# NeopixelRGBVisualizer-Single.net
KiCad netlist of a schematic drawn in EAGLE
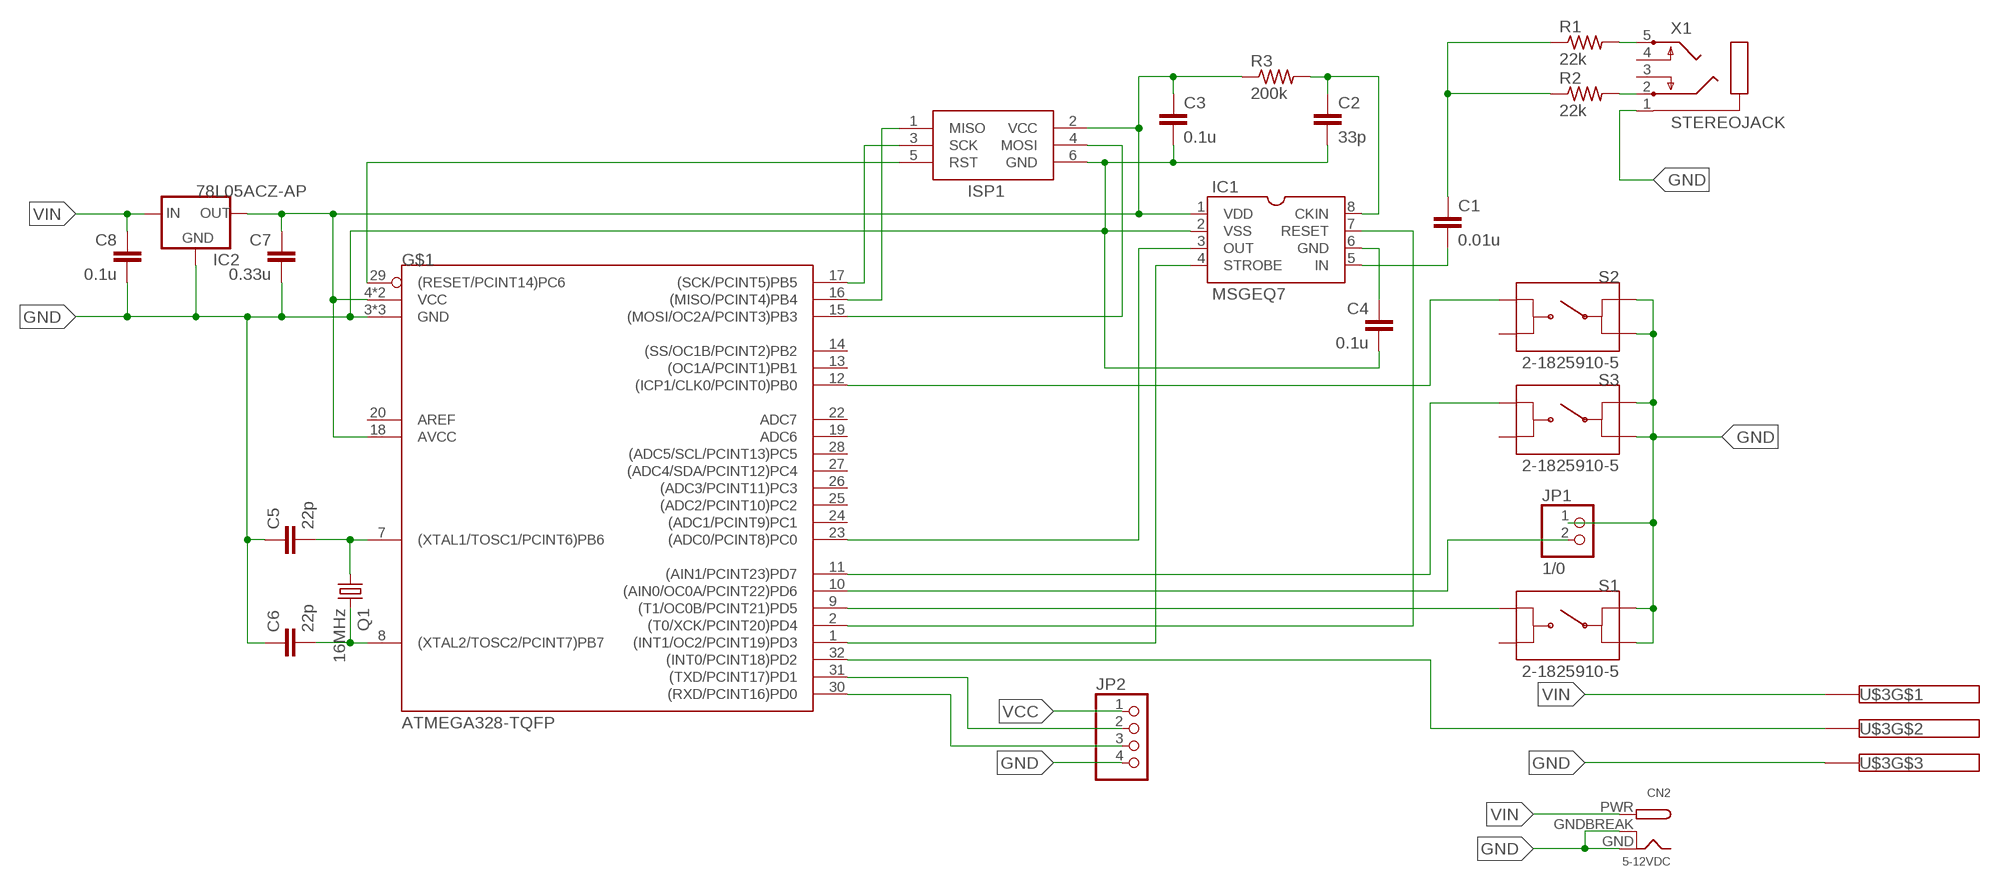
[diagram p0: schematic, sheet 1]

(export (version "E")
  (design (tool "Eeschema 10.0.6"))
  (components
    (comp (ref "C1")
      (value "0.01u")
      (footprint "eagle-import:C0805")
      (libsource (lib "eagle-import") (part "C-EUC0805"))
    )
    (comp (ref "C2")
      (value "33p")
      (footprint "eagle-import:C0805")
      (libsource (lib "eagle-import") (part "C-EUC0805"))
    )
    (comp (ref "C3")
      (value "0.1u")
      (footprint "eagle-import:C0805")
      (libsource (lib "eagle-import") (part "C-EUC0805"))
    )
    (comp (ref "C4")
      (value "0.1u")
      (footprint "eagle-import:C0805")
      (libsource (lib "eagle-import") (part "C-EUC0805"))
    )
    (comp (ref "C5")
      (value "22p")
      (footprint "eagle-import:C0805")
      (libsource (lib "eagle-import") (part "C-EUC0805"))
    )
    (comp (ref "C6")
      (value "22p")
      (footprint "eagle-import:C0805")
      (libsource (lib "eagle-import") (part "C-EUC0805"))
    )
    (comp (ref "C7")
      (value "0.33u")
      (footprint "eagle-import:C0805")
      (libsource (lib "eagle-import") (part "C-EUC0805"))
    )
    (comp (ref "C8")
      (value "0.1u")
      (footprint "eagle-import:C0805")
      (libsource (lib "eagle-import") (part "C-EUC0805"))
    )
    (comp (ref "CN2")
      (value "5-12VDC")
      (footprint "eagle-import:DCJACK_2MM_PTH")
      (libsource (lib "eagle-import") (part "DCBARRELPTH"))
    )
    (comp (ref "IC1")
      (value "MSGEQ7")
      (footprint "eagle-import:DIL08")
      (libsource (lib "eagle-import") (part "MSGEQ7"))
    )
    (comp (ref "IC2")
      (value "78L05ACZ-AP")
      (footprint "eagle-import:78LXX")
      (libsource (lib "eagle-import") (part "78LXX"))
    )
    (comp (ref "ISP1")
      (value "AVRISP-6")
      (footprint "eagle-import:AVRISP")
      (libsource (lib "eagle-import") (part "AVRISP-6"))
    )
    (comp (ref "JP1")
      (value "1/0")
      (footprint "eagle-import:1X02-ROUND")
      (libsource (lib "eagle-import") (part "PINHD-1X2/ROUND"))
    )
    (comp (ref "JP2")
      (value "PINHD-1X4/OCT")
      (footprint "eagle-import:1X04-OCT")
      (libsource (lib "eagle-import") (part "PINHD-1X4/OCT"))
    )
    (comp (ref "Q1")
      (value "16MHz")
      (footprint "eagle-import:CTS406")
      (libsource (lib "eagle-import") (part "CRYSTALCTS406"))
    )
    (comp (ref "R1")
      (value "22k")
      (footprint "eagle-import:M0805")
      (libsource (lib "eagle-import") (part "R-US_M0805"))
    )
    (comp (ref "R2")
      (value "22k")
      (footprint "eagle-import:M0805")
      (libsource (lib "eagle-import") (part "R-US_M0805"))
    )
    (comp (ref "R3")
      (value "200k")
      (footprint "eagle-import:M0805")
      (libsource (lib "eagle-import") (part "R-US_M0805"))
    )
    (comp (ref "S1")
      (value "2-1825910-5")
      (footprint "eagle-import:SW_2-1825910")
      (fields (field (name "DIGI-KEY_PART_NUMBER") "450-1644-ND") (field (name "MF") "TE Connectivity"))
      (libsource (lib "eagle-import") (part "2-1825910-5"))
    )
    (comp (ref "S2")
      (value "2-1825910-5")
      (footprint "eagle-import:SW_2-1825910")
      (fields (field (name "DIGI-KEY_PART_NUMBER") "450-1644-ND") (field (name "MF") "TE Connectivity"))
      (libsource (lib "eagle-import") (part "2-1825910-5"))
    )
    (comp (ref "S3")
      (value "2-1825910-5")
      (footprint "eagle-import:SW_2-1825910")
      (fields (field (name "DIGI-KEY_PART_NUMBER") "450-1644-ND") (field (name "MF") "TE Connectivity"))
      (libsource (lib "eagle-import") (part "2-1825910-5"))
    )
    (comp (ref "U$1")
      (value "ATMEGA328-TQFP")
      (footprint "eagle-import:32M1-A")
      (libsource (lib "eagle-import") (part "ATMEGA328-TQFP"))
    )
    (comp (ref "U$3")
      (value "0039303035")
      (footprint "eagle-import:4.2MM-3PIN")
      (libsource (lib "eagle-import") (part "0039303035"))
    )
    (comp (ref "X1")
      (value "STEREOJACK")
      (footprint "eagle-import:STX3100")
      (libsource (lib "eagle-import") (part "STEREOJACK"))
    )
  )
  (nets
    (net (code "1") (name "GND") (class "Default")
      (node (ref "C2") (pin "2") (pinfunction "2_2") (pintype "passive"))
      (node (ref "C3") (pin "2") (pinfunction "2_2") (pintype "passive"))
      (node (ref "C4") (pin "2") (pinfunction "2_2") (pintype "passive"))
      (node (ref "C5") (pin "1") (pinfunction "1_1") (pintype "passive"))
      (node (ref "C6") (pin "1") (pinfunction "1_1") (pintype "passive"))
      (node (ref "C7") (pin "2") (pinfunction "2_2") (pintype "passive"))
      (node (ref "C8") (pin "2") (pinfunction "2_2") (pintype "passive"))
      (node (ref "CN2") (pin "GND") (pinfunction "GND_GND") (pintype "power_in"))
      (node (ref "CN2") (pin "GNDBREAK") (pinfunction "GNDBREAK_GNDBREAK") (pintype "power_in"))
      (node (ref "IC1") (pin "2") (pinfunction "VSS_2") (pintype "passive"))
      (node (ref "IC2") (pin "GND") (pinfunction "GND_GND") (pintype "input"))
      (node (ref "ISP1") (pin "6") (pinfunction "GND_6") (pintype "power_in"))
      (node (ref "JP1") (pin "1") (pinfunction "1_1") (pintype "passive"))
      (node (ref "JP2") (pin "4") (pinfunction "4_4") (pintype "passive"))
      (node (ref "S1") (pin "1") (pinfunction "1_1") (pintype "passive"))
      (node (ref "S1") (pin "3") (pinfunction "3_3") (pintype "passive"))
      (node (ref "S2") (pin "1") (pinfunction "1_1") (pintype "passive"))
      (node (ref "S2") (pin "3") (pinfunction "3_3") (pintype "passive"))
      (node (ref "S3") (pin "1") (pinfunction "1_1") (pintype "passive"))
      (node (ref "S3") (pin "3") (pinfunction "3_3") (pintype "passive"))
      (node (ref "U$1") (pin "21") (pinfunction "GND_21") (pintype "bidirectional"))
      (node (ref "U$1") (pin "3") (pinfunction "GND_3") (pintype "bidirectional"))
      (node (ref "U$1") (pin "5") (pinfunction "GND_5") (pintype "bidirectional"))
      (node (ref "U$3") (pin "P$3") (pinfunction "P$1_P$3") (pintype "bidirectional"))
      (node (ref "X1") (pin "1") (pinfunction "1_1") (pintype "passive"))
    )
    (net (code "2") (name "Net-(C1-Pad1)") (class "Default")
      (node (ref "C1") (pin "1") (pinfunction "1_1") (pintype "passive"))
      (node (ref "R1") (pin "1") (pinfunction "1_1") (pintype "passive"))
      (node (ref "R2") (pin "1") (pinfunction "1_1") (pintype "passive"))
    )
    (net (code "3") (name "Net-(IC1-CKIN)") (class "Default")
      (node (ref "C2") (pin "1") (pinfunction "1_1") (pintype "passive"))
      (node (ref "IC1") (pin "8") (pinfunction "CKIN_8") (pintype "passive"))
      (node (ref "R3") (pin "2") (pinfunction "2_2") (pintype "passive"))
    )
    (net (code "4") (name "Net-(IC1-GND)") (class "Default")
      (node (ref "C4") (pin "1") (pinfunction "1_1") (pintype "passive"))
      (node (ref "IC1") (pin "6") (pinfunction "GND_6") (pintype "passive"))
    )
    (net (code "5") (name "Net-(IC1-IN)") (class "Default")
      (node (ref "C1") (pin "2") (pinfunction "2_2") (pintype "passive"))
      (node (ref "IC1") (pin "5") (pinfunction "IN_5") (pintype "passive"))
    )
    (net (code "6") (name "Net-(IC1-OUT)") (class "Default")
      (node (ref "IC1") (pin "3") (pinfunction "OUT_3") (pintype "passive"))
      (node (ref "U$1") (pin "23") (pinfunction "(ADC0/PCINT8)PC0_23") (pintype "bidirectional"))
    )
    (net (code "7") (name "Net-(IC1-RESET)") (class "Default")
      (node (ref "IC1") (pin "7") (pinfunction "RESET_7") (pintype "passive"))
      (node (ref "U$1") (pin "2") (pinfunction "(T0/XCK/PCINT20)PD4_2") (pintype "bidirectional"))
    )
    (net (code "8") (name "Net-(IC1-STROBE)") (class "Default")
      (node (ref "IC1") (pin "4") (pinfunction "STROBE_4") (pintype "passive"))
      (node (ref "U$1") (pin "1") (pinfunction "(INT1/OC2/PCINT19)PD3_1") (pintype "bidirectional"))
    )
    (net (code "9") (name "Net-(ISP1-MISO)") (class "Default")
      (node (ref "ISP1") (pin "1") (pinfunction "MISO_1") (pintype "input"))
      (node (ref "U$1") (pin "16") (pinfunction "(MISO/PCINT4)PB4_16") (pintype "bidirectional"))
    )
    (net (code "10") (name "Net-(ISP1-MOSI)") (class "Default")
      (node (ref "ISP1") (pin "4") (pinfunction "MOSI_4") (pintype "output"))
      (node (ref "U$1") (pin "15") (pinfunction "(MOSI/OC2A/PCINT3)PB3_15") (pintype "bidirectional"))
    )
    (net (code "11") (name "Net-(ISP1-RST)") (class "Default")
      (node (ref "ISP1") (pin "5") (pinfunction "RST_5") (pintype "output"))
      (node (ref "U$1") (pin "29") (pinfunction "(RESET/PCINT14)PC6_29") (pintype "bidirectional"))
    )
    (net (code "12") (name "Net-(ISP1-SCK)") (class "Default")
      (node (ref "ISP1") (pin "3") (pinfunction "SCK_3") (pintype "output"))
      (node (ref "U$1") (pin "17") (pinfunction "(SCK/PCINT5)PB5_17") (pintype "bidirectional"))
    )
    (net (code "13") (name "Net-(Q1-2)") (class "Default")
      (node (ref "C6") (pin "2") (pinfunction "2_2") (pintype "passive"))
      (node (ref "Q1") (pin "3") (pinfunction "2_3") (pintype "passive"))
      (node (ref "U$1") (pin "8") (pinfunction "(XTAL2/TOSC2/PCINT7)PB7_8") (pintype "bidirectional"))
    )
    (net (code "14") (name "Net-(R1-Pad2)") (class "Default")
      (node (ref "R1") (pin "2") (pinfunction "2_2") (pintype "passive"))
      (node (ref "X1") (pin "5") (pinfunction "5_5") (pintype "passive"))
    )
    (net (code "15") (name "Net-(R2-Pad2)") (class "Default")
      (node (ref "R2") (pin "2") (pinfunction "2_2") (pintype "passive"))
      (node (ref "X1") (pin "2") (pinfunction "2_2") (pintype "passive"))
    )
    (net (code "16") (name "Net-(U$1-(AIN0{slash}OC0A{slash}PCINT22)PD6)") (class "Default")
      (node (ref "JP1") (pin "2") (pinfunction "2_2") (pintype "passive"))
      (node (ref "U$1") (pin "10") (pinfunction "(AIN0/OC0A/PCINT22)PD6_10") (pintype "bidirectional"))
    )
    (net (code "17") (name "Net-(U$1-(AIN1{slash}PCINT23)PD7)") (class "Default")
      (node (ref "S3") (pin "2") (pinfunction "2_2") (pintype "passive"))
      (node (ref "U$1") (pin "11") (pinfunction "(AIN1/PCINT23)PD7_11") (pintype "bidirectional"))
    )
    (net (code "18") (name "Net-(U$1-(ICP1{slash}CLK0{slash}PCINT0)PB0)") (class "Default")
      (node (ref "S2") (pin "2") (pinfunction "2_2") (pintype "passive"))
      (node (ref "U$1") (pin "12") (pinfunction "(ICP1/CLK0/PCINT0)PB0_12") (pintype "bidirectional"))
    )
    (net (code "19") (name "Net-(U$1-(INT0{slash}PCINT18)PD2)") (class "Default")
      (node (ref "U$1") (pin "32") (pinfunction "(INT0/PCINT18)PD2_32") (pintype "bidirectional"))
      (node (ref "U$3") (pin "P$2") (pinfunction "P$1_P$2") (pintype "bidirectional"))
    )
    (net (code "20") (name "Net-(U$1-(RXD{slash}PCINT16)PD0)") (class "Default")
      (node (ref "JP2") (pin "3") (pinfunction "3_3") (pintype "passive"))
      (node (ref "U$1") (pin "30") (pinfunction "(RXD/PCINT16)PD0_30") (pintype "bidirectional"))
    )
    (net (code "21") (name "Net-(U$1-(T1{slash}OC0B{slash}PCINT21)PD5)") (class "Default")
      (node (ref "S1") (pin "2") (pinfunction "2_2") (pintype "passive"))
      (node (ref "U$1") (pin "9") (pinfunction "(T1/OC0B/PCINT21)PD5_9") (pintype "bidirectional"))
    )
    (net (code "22") (name "Net-(U$1-(TXD{slash}PCINT17)PD1)") (class "Default")
      (node (ref "JP2") (pin "2") (pinfunction "2_2") (pintype "passive"))
      (node (ref "U$1") (pin "31") (pinfunction "(TXD/PCINT17)PD1_31") (pintype "bidirectional"))
    )
    (net (code "23") (name "Net-(U$1-(XTAL1{slash}TOSC1{slash}PCINT6)PB6)") (class "Default")
      (node (ref "C5") (pin "2") (pinfunction "2_2") (pintype "passive"))
      (node (ref "Q1") (pin "1") (pinfunction "1_1") (pintype "passive"))
      (node (ref "U$1") (pin "7") (pinfunction "(XTAL1/TOSC1/PCINT6)PB6_7") (pintype "bidirectional"))
    )
    (net (code "24") (name "VCC") (class "Default")
      (node (ref "C3") (pin "1") (pinfunction "1_1") (pintype "passive"))
      (node (ref "C7") (pin "1") (pinfunction "1_1") (pintype "passive"))
      (node (ref "IC1") (pin "1") (pinfunction "VDD_1") (pintype "passive"))
      (node (ref "IC2") (pin "OUT") (pinfunction "OUT_OUT") (pintype "passive"))
      (node (ref "ISP1") (pin "2") (pinfunction "VCC_2") (pintype "power_in"))
      (node (ref "JP2") (pin "1") (pinfunction "1_1") (pintype "passive"))
      (node (ref "R3") (pin "1") (pinfunction "1_1") (pintype "passive"))
      (node (ref "U$1") (pin "18") (pinfunction "AVCC_18") (pintype "bidirectional"))
      (node (ref "U$1") (pin "4") (pinfunction "VCC_4") (pintype "bidirectional"))
      (node (ref "U$1") (pin "6") (pinfunction "VCC_6") (pintype "bidirectional"))
    )
    (net (code "25") (name "VIN") (class "Default")
      (node (ref "C8") (pin "1") (pinfunction "1_1") (pintype "passive"))
      (node (ref "CN2") (pin "PWR") (pinfunction "PWR_PWR") (pintype "power_in"))
      (node (ref "IC2") (pin "IN") (pinfunction "IN_IN") (pintype "input"))
      (node (ref "U$3") (pin "P$1") (pinfunction "P$1_P$1") (pintype "bidirectional"))
    )
    (net (code "26") (name "unconnected-(S1-Pad4)") (class "Default")
      (node (ref "S1") (pin "4") (pinfunction "4_4") (pintype "passive"))
    )
    (net (code "27") (name "unconnected-(S2-Pad4)") (class "Default")
      (node (ref "S2") (pin "4") (pinfunction "4_4") (pintype "passive"))
    )
    (net (code "28") (name "unconnected-(S3-Pad4)") (class "Default")
      (node (ref "S3") (pin "4") (pinfunction "4_4") (pintype "passive"))
    )
    (net (code "29") (name "unconnected-(U$1-(ADC1{slash}PCINT9)PC1-Pad24)") (class "Default")
      (node (ref "U$1") (pin "24") (pinfunction "(ADC1/PCINT9)PC1_24") (pintype "bidirectional"))
    )
    (net (code "30") (name "unconnected-(U$1-(ADC2{slash}PCINT10)PC2-Pad25)") (class "Default")
      (node (ref "U$1") (pin "25") (pinfunction "(ADC2/PCINT10)PC2_25") (pintype "bidirectional"))
    )
    (net (code "31") (name "unconnected-(U$1-(ADC3{slash}PCINT11)PC3-Pad26)") (class "Default")
      (node (ref "U$1") (pin "26") (pinfunction "(ADC3/PCINT11)PC3_26") (pintype "bidirectional"))
    )
    (net (code "32") (name "unconnected-(U$1-(ADC4{slash}SDA{slash}PCINT12)PC4-Pad27)") (class "Default")
      (node (ref "U$1") (pin "27") (pinfunction "(ADC4/SDA/PCINT12)PC4_27") (pintype "bidirectional"))
    )
    (net (code "33") (name "unconnected-(U$1-(ADC5{slash}SCL{slash}PCINT13)PC5-Pad28)") (class "Default")
      (node (ref "U$1") (pin "28") (pinfunction "(ADC5/SCL/PCINT13)PC5_28") (pintype "bidirectional"))
    )
    (net (code "34") (name "unconnected-(U$1-(OC1A{slash}PCINT1)PB1-Pad13)") (class "Default")
      (node (ref "U$1") (pin "13") (pinfunction "(OC1A/PCINT1)PB1_13") (pintype "bidirectional"))
    )
    (net (code "35") (name "unconnected-(U$1-(SS{slash}OC1B{slash}PCINT2)PB2-Pad14)") (class "Default")
      (node (ref "U$1") (pin "14") (pinfunction "(SS/OC1B/PCINT2)PB2_14") (pintype "bidirectional"))
    )
    (net (code "36") (name "unconnected-(U$1-ADC6-Pad19)") (class "Default")
      (node (ref "U$1") (pin "19") (pinfunction "ADC6_19") (pintype "bidirectional"))
    )
    (net (code "37") (name "unconnected-(U$1-ADC7-Pad22)") (class "Default")
      (node (ref "U$1") (pin "22") (pinfunction "ADC7_22") (pintype "bidirectional"))
    )
    (net (code "38") (name "unconnected-(U$1-AREF-Pad20)") (class "Default")
      (node (ref "U$1") (pin "20") (pinfunction "AREF_20") (pintype "bidirectional"))
    )
    (net (code "39") (name "unconnected-(X1-Pad3)") (class "Default")
      (node (ref "X1") (pin "3") (pinfunction "3_3") (pintype "passive"))
    )
    (net (code "40") (name "unconnected-(X1-Pad4)") (class "Default")
      (node (ref "X1") (pin "4") (pinfunction "4_4") (pintype "passive"))
    )
  )
)
